# snc98_Display_15x7-Segment_LED.net
KiCad netlist of a schematic drawn in EAGLE
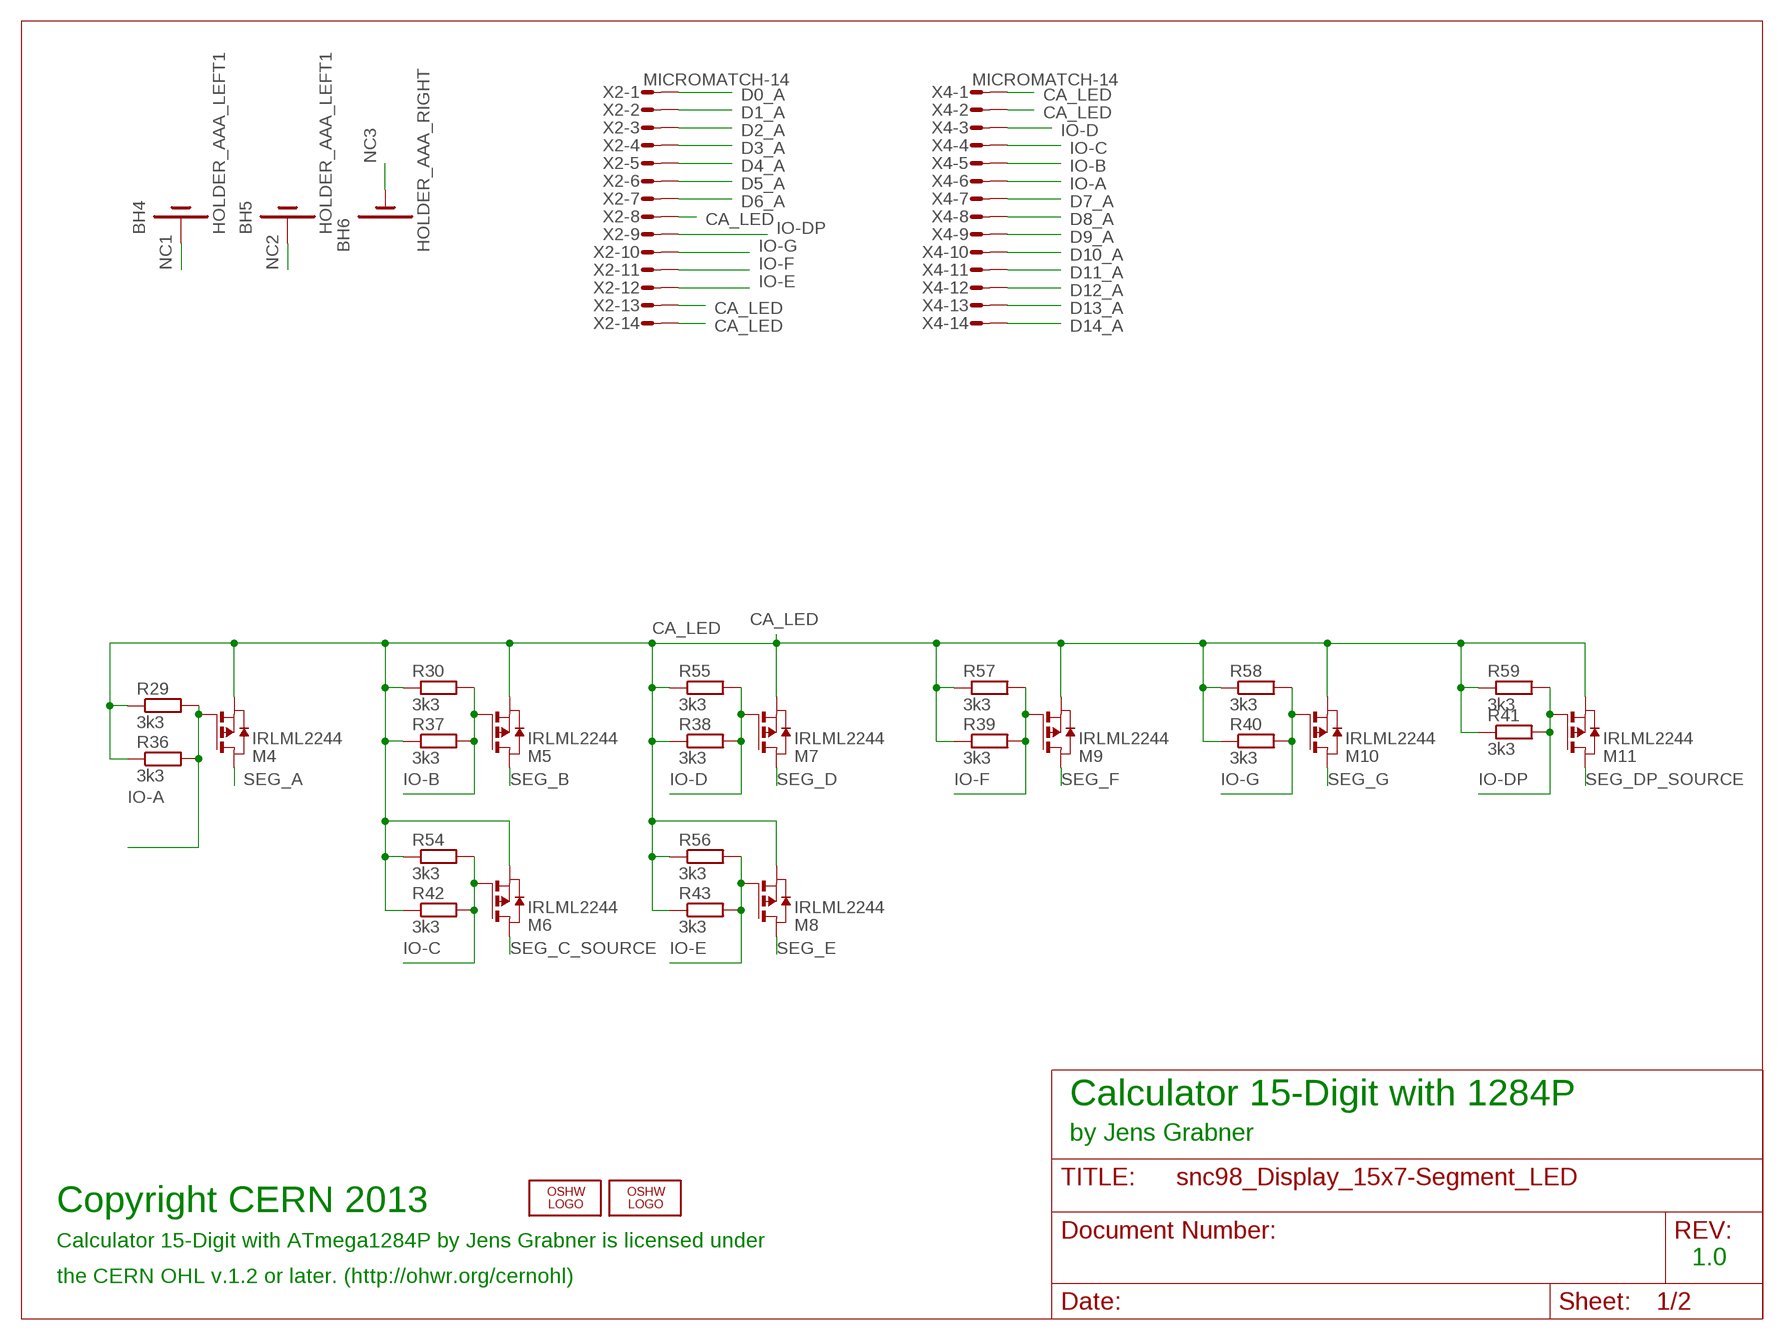
[diagram p0: schematic, sheet 1]
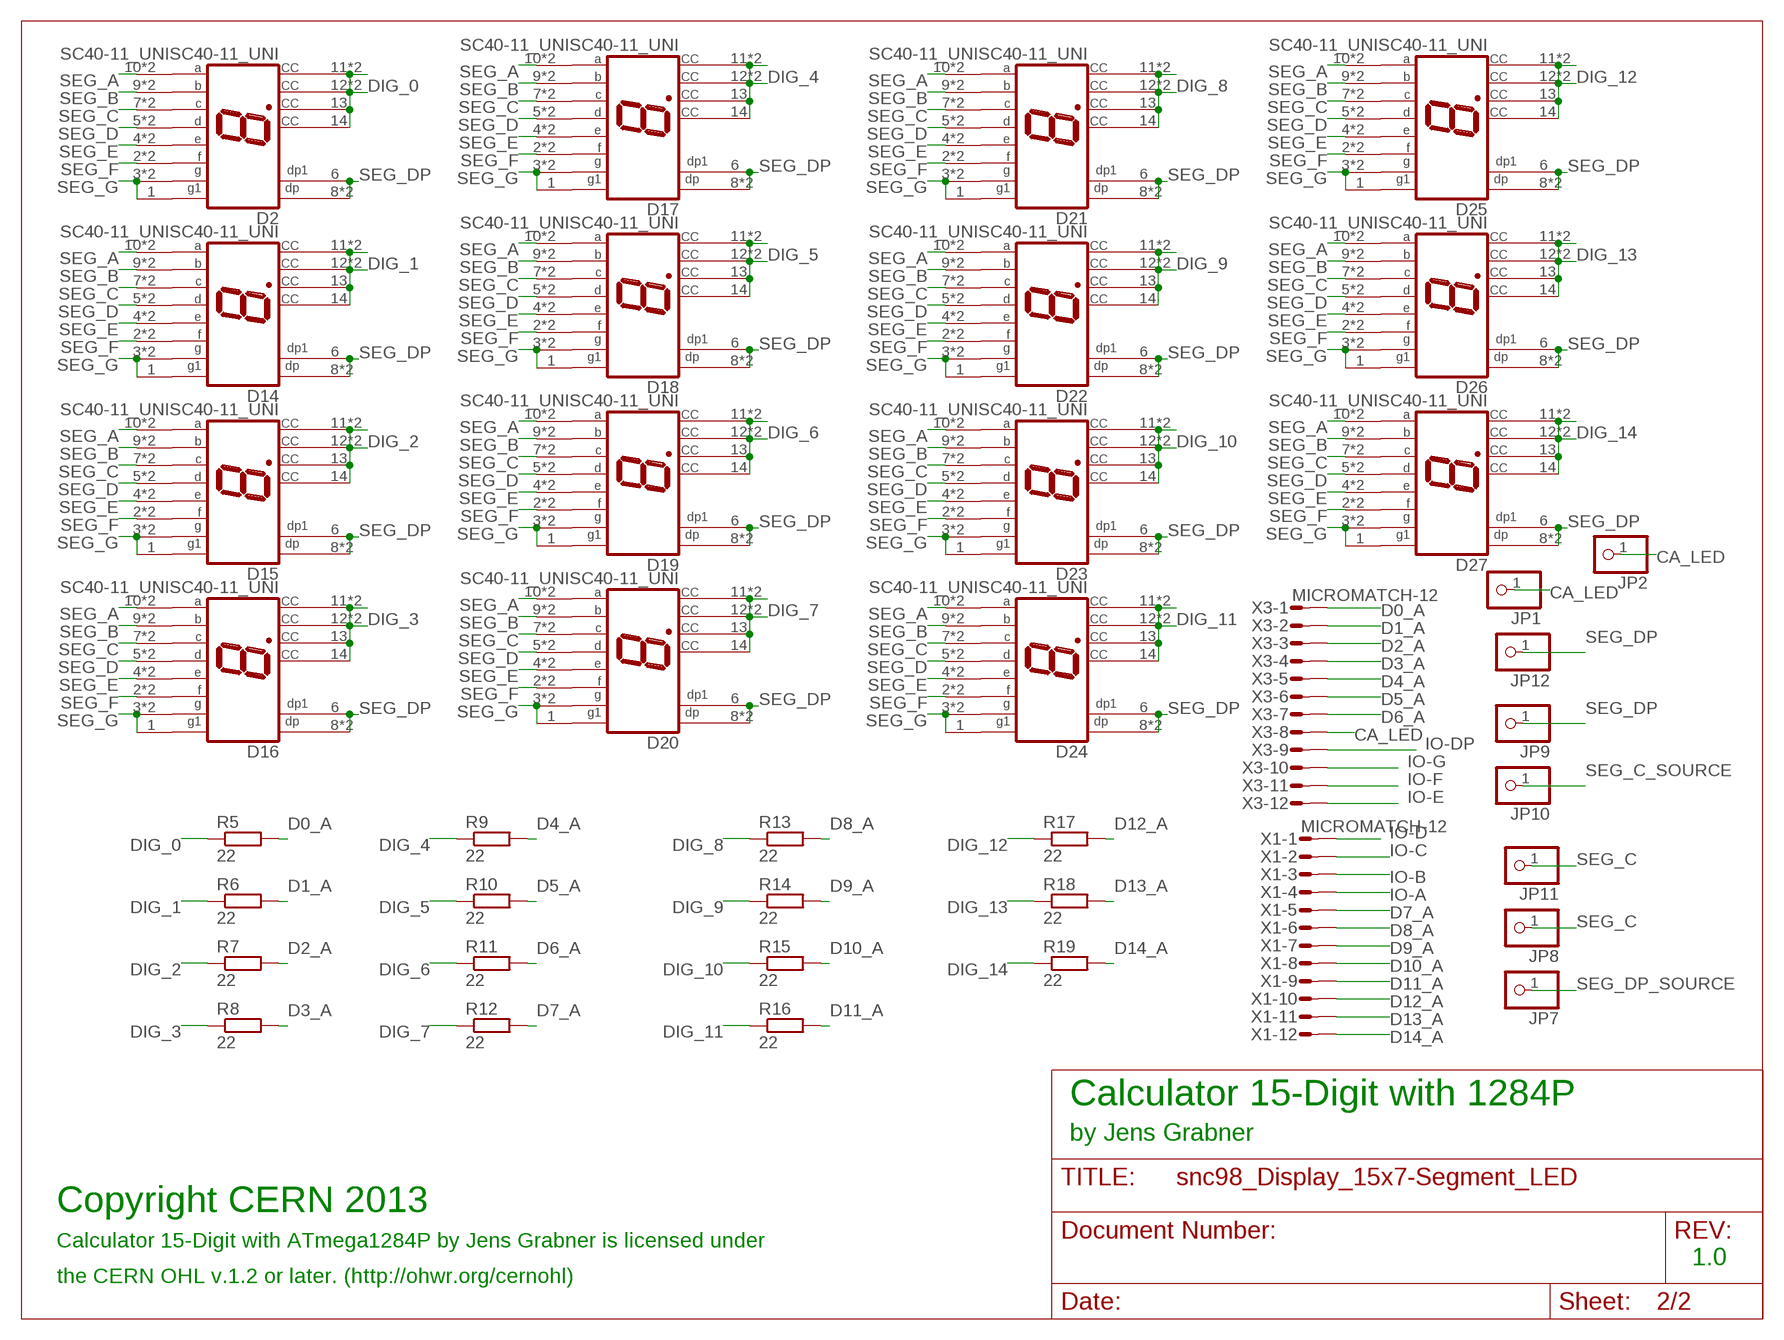
[diagram p1: schematic, sheet 2]

(export (version "E")
  (design (tool "Eeschema 10.0.6"))
  (components
    (comp (ref "BH4")
      (value "HOLDER_AAA_LEFT1")
      (footprint "eagle-import:BATTERY-AAA-LEFT")
      (libsource (lib "eagle-import") (part "HOLDER_AAA_LEFT1"))
    )
    (comp (ref "BH5")
      (value "HOLDER_AAA_LEFT1")
      (footprint "eagle-import:BATTERY-AAA-LEFT")
      (libsource (lib "eagle-import") (part "HOLDER_AAA_LEFT1"))
    )
    (comp (ref "BH6")
      (value "HOLDER_AAA_RIGHT")
      (footprint "eagle-import:BATTERY-AAA-RIGHT")
      (libsource (lib "eagle-import") (part "HOLDER_AAA_RIGHT"))
    )
    (comp (ref "LOGO1")
      (value "OSHW_LOGO_8MILX0150-NT")
      (footprint "eagle-import:OSHW_8X150_NOTEXT")
      (libsource (lib "eagle-import") (part "OSHW_LOGO_8MILX0150-NT"))
    )
    (comp (ref "LOGO3")
      (value "OSHW_LOGO_6MILX0100-NT")
      (footprint "eagle-import:OSHW_6X100_NOTEXT")
      (libsource (lib "eagle-import") (part "OSHW_LOGO_6MILX0100-NT"))
    )
    (comp (ref "M4")
      (value "IRLML2244")
      (footprint "eagle-import:SOT-23")
      (libsource (lib "eagle-import") (part "IRLML6402"))
    )
    (comp (ref "M5")
      (value "IRLML2244")
      (footprint "eagle-import:SOT-23")
      (libsource (lib "eagle-import") (part "IRLML6402"))
    )
    (comp (ref "M6")
      (value "IRLML2244")
      (footprint "eagle-import:SOT-23")
      (libsource (lib "eagle-import") (part "IRLML6402"))
    )
    (comp (ref "M7")
      (value "IRLML2244")
      (footprint "eagle-import:SOT-23")
      (libsource (lib "eagle-import") (part "IRLML6402"))
    )
    (comp (ref "M8")
      (value "IRLML2244")
      (footprint "eagle-import:SOT-23")
      (libsource (lib "eagle-import") (part "IRLML6402"))
    )
    (comp (ref "M9")
      (value "IRLML2244")
      (footprint "eagle-import:SOT-23")
      (libsource (lib "eagle-import") (part "IRLML6402"))
    )
    (comp (ref "M10")
      (value "IRLML2244")
      (footprint "eagle-import:SOT-23")
      (libsource (lib "eagle-import") (part "IRLML6402"))
    )
    (comp (ref "M11")
      (value "IRLML2244")
      (footprint "eagle-import:SOT-23")
      (libsource (lib "eagle-import") (part "IRLML6402"))
    )
    (comp (ref "R29")
      (value "3k3")
      (footprint "eagle-import:0204_5")
      (libsource (lib "eagle-import") (part "R-EU_0204/5"))
    )
    (comp (ref "R30")
      (value "3k3")
      (footprint "eagle-import:0204_5")
      (libsource (lib "eagle-import") (part "R-EU_0204/5"))
    )
    (comp (ref "R36")
      (value "3k3")
      (footprint "eagle-import:R1206")
      (libsource (lib "eagle-import") (part "R-EU_R1206"))
    )
    (comp (ref "R37")
      (value "3k3")
      (footprint "eagle-import:R1206")
      (libsource (lib "eagle-import") (part "R-EU_R1206"))
    )
    (comp (ref "R38")
      (value "3k3")
      (footprint "eagle-import:R1206")
      (libsource (lib "eagle-import") (part "R-EU_R1206"))
    )
    (comp (ref "R39")
      (value "3k3")
      (footprint "eagle-import:R1206")
      (libsource (lib "eagle-import") (part "R-EU_R1206"))
    )
    (comp (ref "R40")
      (value "3k3")
      (footprint "eagle-import:R1206")
      (libsource (lib "eagle-import") (part "R-EU_R1206"))
    )
    (comp (ref "R41")
      (value "3k3")
      (footprint "eagle-import:R1206")
      (libsource (lib "eagle-import") (part "R-EU_R1206"))
    )
    (comp (ref "R42")
      (value "3k3")
      (footprint "eagle-import:R1206")
      (libsource (lib "eagle-import") (part "R-EU_R1206"))
    )
    (comp (ref "R43")
      (value "3k3")
      (footprint "eagle-import:R1206")
      (libsource (lib "eagle-import") (part "R-EU_R1206"))
    )
    (comp (ref "R54")
      (value "3k3")
      (footprint "eagle-import:0204_5")
      (libsource (lib "eagle-import") (part "R-EU_0204/5"))
    )
    (comp (ref "R55")
      (value "3k3")
      (footprint "eagle-import:0204_5")
      (libsource (lib "eagle-import") (part "R-EU_0204/5"))
    )
    (comp (ref "R56")
      (value "3k3")
      (footprint "eagle-import:0204_5")
      (libsource (lib "eagle-import") (part "R-EU_0204/5"))
    )
    (comp (ref "R57")
      (value "3k3")
      (footprint "eagle-import:0204_5")
      (libsource (lib "eagle-import") (part "R-EU_0204/5"))
    )
    (comp (ref "R58")
      (value "3k3")
      (footprint "eagle-import:0204_5")
      (libsource (lib "eagle-import") (part "R-EU_0204/5"))
    )
    (comp (ref "R59")
      (value "3k3")
      (footprint "eagle-import:0204_5")
      (libsource (lib "eagle-import") (part "R-EU_0204/5"))
    )
    (comp (ref "X2")
      (value "MICROMATCH-14")
      (footprint "eagle-import:MICROMATCH-14")
      (fields (field (name "MF") "FARNELL") (field (name "MPN") "8-215464-4"))
      (libsource (lib "eagle-import") (part "MICROMATCH-14"))
    )
    (comp (ref "X4")
      (value "MICROMATCH-14")
      (footprint "eagle-import:MICROMATCH-14")
      (fields (field (name "MF") "FARNELL") (field (name "MPN") "8-215464-4"))
      (libsource (lib "eagle-import") (part "MICROMATCH-14"))
    )
    (comp (ref "D2")
      (value "SC40-11_UNISC40-11_UNI")
      (footprint "eagle-import:10MM_UNI")
      (libsource (lib "eagle-import") (part "SC40-11_UNISC40-11_UNI"))
    )
    (comp (ref "D14")
      (value "SC40-11_UNISC40-11_UNI")
      (footprint "eagle-import:10MM_UNI")
      (libsource (lib "eagle-import") (part "SC40-11_UNISC40-11_UNI"))
    )
    (comp (ref "D15")
      (value "SC40-11_UNISC40-11_UNI")
      (footprint "eagle-import:10MM_UNI")
      (libsource (lib "eagle-import") (part "SC40-11_UNISC40-11_UNI"))
    )
    (comp (ref "D16")
      (value "SC40-11_UNISC40-11_UNI")
      (footprint "eagle-import:10MM_UNI")
      (libsource (lib "eagle-import") (part "SC40-11_UNISC40-11_UNI"))
    )
    (comp (ref "D17")
      (value "SC40-11_UNISC40-11_UNI")
      (footprint "eagle-import:10MM_UNI")
      (libsource (lib "eagle-import") (part "SC40-11_UNISC40-11_UNI"))
    )
    (comp (ref "D18")
      (value "SC40-11_UNISC40-11_UNI")
      (footprint "eagle-import:10MM_UNI")
      (libsource (lib "eagle-import") (part "SC40-11_UNISC40-11_UNI"))
    )
    (comp (ref "D19")
      (value "SC40-11_UNISC40-11_UNI")
      (footprint "eagle-import:10MM_UNI")
      (libsource (lib "eagle-import") (part "SC40-11_UNISC40-11_UNI"))
    )
    (comp (ref "D20")
      (value "SC40-11_UNISC40-11_UNI")
      (footprint "eagle-import:10MM_UNI")
      (libsource (lib "eagle-import") (part "SC40-11_UNISC40-11_UNI"))
    )
    (comp (ref "D21")
      (value "SC40-11_UNISC40-11_UNI")
      (footprint "eagle-import:10MM_UNI")
      (libsource (lib "eagle-import") (part "SC40-11_UNISC40-11_UNI"))
    )
    (comp (ref "D22")
      (value "SC40-11_UNISC40-11_UNI")
      (footprint "eagle-import:10MM_UNI")
      (libsource (lib "eagle-import") (part "SC40-11_UNISC40-11_UNI"))
    )
    (comp (ref "D23")
      (value "SC40-11_UNISC40-11_UNI")
      (footprint "eagle-import:10MM_UNI")
      (libsource (lib "eagle-import") (part "SC40-11_UNISC40-11_UNI"))
    )
    (comp (ref "D24")
      (value "SC40-11_UNISC40-11_UNI")
      (footprint "eagle-import:10MM_UNI")
      (libsource (lib "eagle-import") (part "SC40-11_UNISC40-11_UNI"))
    )
    (comp (ref "D25")
      (value "SC40-11_UNISC40-11_UNI")
      (footprint "eagle-import:10MM_UNI")
      (libsource (lib "eagle-import") (part "SC40-11_UNISC40-11_UNI"))
    )
    (comp (ref "D26")
      (value "SC40-11_UNISC40-11_UNI")
      (footprint "eagle-import:10MM_UNI")
      (libsource (lib "eagle-import") (part "SC40-11_UNISC40-11_UNI"))
    )
    (comp (ref "D27")
      (value "SC40-11_UNISC40-11_UNI")
      (footprint "eagle-import:10MM_UNI")
      (libsource (lib "eagle-import") (part "SC40-11_UNISC40-11_UNI"))
    )
    (comp (ref "JP1")
      (value "PINHD-1X1")
      (footprint "eagle-import:1X01")
      (libsource (lib "eagle-import") (part "PINHD-1X1"))
    )
    (comp (ref "JP2")
      (value "PINHD-1X1")
      (footprint "eagle-import:1X01")
      (libsource (lib "eagle-import") (part "PINHD-1X1"))
    )
    (comp (ref "JP7")
      (value "PINHD-1X1")
      (footprint "eagle-import:1X01")
      (libsource (lib "eagle-import") (part "PINHD-1X1"))
    )
    (comp (ref "JP8")
      (value "PINHD-1X1")
      (footprint "eagle-import:1X01")
      (libsource (lib "eagle-import") (part "PINHD-1X1"))
    )
    (comp (ref "JP9")
      (value "PINHD-1X1")
      (footprint "eagle-import:1X01")
      (libsource (lib "eagle-import") (part "PINHD-1X1"))
    )
    (comp (ref "JP10")
      (value "PINHD-1X1")
      (footprint "eagle-import:1X01")
      (libsource (lib "eagle-import") (part "PINHD-1X1"))
    )
    (comp (ref "JP11")
      (value "PINHD-1X1")
      (footprint "eagle-import:1X01")
      (libsource (lib "eagle-import") (part "PINHD-1X1"))
    )
    (comp (ref "JP12")
      (value "PINHD-1X1")
      (footprint "eagle-import:1X01")
      (libsource (lib "eagle-import") (part "PINHD-1X1"))
    )
    (comp (ref "R5")
      (value "22")
      (footprint "eagle-import:R1210")
      (libsource (lib "eagle-import") (part "R-EU_R1210"))
    )
    (comp (ref "R6")
      (value "22")
      (footprint "eagle-import:R1210")
      (libsource (lib "eagle-import") (part "R-EU_R1210"))
    )
    (comp (ref "R7")
      (value "22")
      (footprint "eagle-import:R1210")
      (libsource (lib "eagle-import") (part "R-EU_R1210"))
    )
    (comp (ref "R8")
      (value "22")
      (footprint "eagle-import:R1210")
      (libsource (lib "eagle-import") (part "R-EU_R1210"))
    )
    (comp (ref "R9")
      (value "22")
      (footprint "eagle-import:R1210")
      (libsource (lib "eagle-import") (part "R-EU_R1210"))
    )
    (comp (ref "R10")
      (value "22")
      (footprint "eagle-import:R1210")
      (libsource (lib "eagle-import") (part "R-EU_R1210"))
    )
    (comp (ref "R11")
      (value "22")
      (footprint "eagle-import:R1210")
      (libsource (lib "eagle-import") (part "R-EU_R1210"))
    )
    (comp (ref "R12")
      (value "22")
      (footprint "eagle-import:R1210")
      (libsource (lib "eagle-import") (part "R-EU_R1210"))
    )
    (comp (ref "R13")
      (value "22")
      (footprint "eagle-import:R1210")
      (libsource (lib "eagle-import") (part "R-EU_R1210"))
    )
    (comp (ref "R14")
      (value "22")
      (footprint "eagle-import:R1210")
      (libsource (lib "eagle-import") (part "R-EU_R1210"))
    )
    (comp (ref "R15")
      (value "22")
      (footprint "eagle-import:R1210")
      (libsource (lib "eagle-import") (part "R-EU_R1210"))
    )
    (comp (ref "R16")
      (value "22")
      (footprint "eagle-import:R1210")
      (libsource (lib "eagle-import") (part "R-EU_R1210"))
    )
    (comp (ref "R17")
      (value "22")
      (footprint "eagle-import:R1210")
      (libsource (lib "eagle-import") (part "R-EU_R1210"))
    )
    (comp (ref "R18")
      (value "22")
      (footprint "eagle-import:R1210")
      (libsource (lib "eagle-import") (part "R-EU_R1210"))
    )
    (comp (ref "R19")
      (value "22")
      (footprint "eagle-import:R1210")
      (libsource (lib "eagle-import") (part "R-EU_R1210"))
    )
    (comp (ref "X1")
      (value "MICROMATCH-12")
      (footprint "eagle-import:MICROMATCH-12")
      (fields (field (name "MF") "FARNELL") (field (name "MPN") "8-215464-2"))
      (libsource (lib "eagle-import") (part "MICROMATCH-12"))
    )
    (comp (ref "X3")
      (value "MICROMATCH-12")
      (footprint "eagle-import:MICROMATCH-12")
      (fields (field (name "MF") "FARNELL") (field (name "MPN") "8-215464-2"))
      (libsource (lib "eagle-import") (part "MICROMATCH-12"))
    )
  )
  (nets
    (net (code "1") (name "CA_LED") (class "Default")
      (node (ref "JP1") (pin "1") (pinfunction "1_1") (pintype "passive"))
      (node (ref "JP2") (pin "1") (pinfunction "1_1") (pintype "passive"))
      (node (ref "M10") (pin "2") (pinfunction "S_2") (pintype "passive"))
      (node (ref "M11") (pin "2") (pinfunction "S_2") (pintype "passive"))
      (node (ref "M4") (pin "2") (pinfunction "S_2") (pintype "passive"))
      (node (ref "M5") (pin "2") (pinfunction "S_2") (pintype "passive"))
      (node (ref "M6") (pin "2") (pinfunction "S_2") (pintype "passive"))
      (node (ref "M7") (pin "2") (pinfunction "S_2") (pintype "passive"))
      (node (ref "M8") (pin "2") (pinfunction "S_2") (pintype "passive"))
      (node (ref "M9") (pin "2") (pinfunction "S_2") (pintype "passive"))
      (node (ref "R29") (pin "1") (pinfunction "1_1") (pintype "passive"))
      (node (ref "R30") (pin "1") (pinfunction "1_1") (pintype "passive"))
      (node (ref "R36") (pin "1") (pinfunction "1_1") (pintype "passive"))
      (node (ref "R37") (pin "1") (pinfunction "1_1") (pintype "passive"))
      (node (ref "R38") (pin "1") (pinfunction "1_1") (pintype "passive"))
      (node (ref "R39") (pin "1") (pinfunction "1_1") (pintype "passive"))
      (node (ref "R40") (pin "1") (pinfunction "1_1") (pintype "passive"))
      (node (ref "R41") (pin "1") (pinfunction "1_1") (pintype "passive"))
      (node (ref "R42") (pin "1") (pinfunction "1_1") (pintype "passive"))
      (node (ref "R43") (pin "1") (pinfunction "1_1") (pintype "passive"))
      (node (ref "R54") (pin "1") (pinfunction "1_1") (pintype "passive"))
      (node (ref "R55") (pin "1") (pinfunction "1_1") (pintype "passive"))
      (node (ref "R56") (pin "1") (pinfunction "1_1") (pintype "passive"))
      (node (ref "R57") (pin "1") (pinfunction "1_1") (pintype "passive"))
      (node (ref "R58") (pin "1") (pinfunction "1_1") (pintype "passive"))
      (node (ref "R59") (pin "1") (pinfunction "1_1") (pintype "passive"))
      (node (ref "X2") (pin "13") (pinfunction "S_13") (pintype "passive"))
      (node (ref "X2") (pin "14") (pinfunction "S_14") (pintype "passive"))
      (node (ref "X2") (pin "8") (pinfunction "S_8") (pintype "passive"))
      (node (ref "X3") (pin "8") (pinfunction "S_8") (pintype "passive"))
      (node (ref "X4") (pin "1") (pinfunction "S_1") (pintype "passive"))
      (node (ref "X4") (pin "2") (pinfunction "S_2") (pintype "passive"))
    )
    (net (code "2") (name "D0_A") (class "Default")
      (node (ref "R5") (pin "2") (pinfunction "2_2") (pintype "passive"))
      (node (ref "X2") (pin "1") (pinfunction "S_1") (pintype "passive"))
      (node (ref "X3") (pin "1") (pinfunction "S_1") (pintype "passive"))
    )
    (net (code "3") (name "D1_A") (class "Default")
      (node (ref "R6") (pin "2") (pinfunction "2_2") (pintype "passive"))
      (node (ref "X2") (pin "2") (pinfunction "S_2") (pintype "passive"))
      (node (ref "X3") (pin "2") (pinfunction "S_2") (pintype "passive"))
    )
    (net (code "4") (name "D2_A") (class "Default")
      (node (ref "R7") (pin "2") (pinfunction "2_2") (pintype "passive"))
      (node (ref "X2") (pin "3") (pinfunction "S_3") (pintype "passive"))
      (node (ref "X3") (pin "3") (pinfunction "S_3") (pintype "passive"))
    )
    (net (code "5") (name "D3_A") (class "Default")
      (node (ref "R8") (pin "2") (pinfunction "2_2") (pintype "passive"))
      (node (ref "X2") (pin "4") (pinfunction "S_4") (pintype "passive"))
      (node (ref "X3") (pin "4") (pinfunction "S_4") (pintype "passive"))
    )
    (net (code "6") (name "D4_A") (class "Default")
      (node (ref "R9") (pin "2") (pinfunction "2_2") (pintype "passive"))
      (node (ref "X2") (pin "5") (pinfunction "S_5") (pintype "passive"))
      (node (ref "X3") (pin "5") (pinfunction "S_5") (pintype "passive"))
    )
    (net (code "7") (name "D5_A") (class "Default")
      (node (ref "R10") (pin "2") (pinfunction "2_2") (pintype "passive"))
      (node (ref "X2") (pin "6") (pinfunction "S_6") (pintype "passive"))
      (node (ref "X3") (pin "6") (pinfunction "S_6") (pintype "passive"))
    )
    (net (code "8") (name "D6_A") (class "Default")
      (node (ref "R11") (pin "2") (pinfunction "2_2") (pintype "passive"))
      (node (ref "X2") (pin "7") (pinfunction "S_7") (pintype "passive"))
      (node (ref "X3") (pin "7") (pinfunction "S_7") (pintype "passive"))
    )
    (net (code "9") (name "D7_A") (class "Default")
      (node (ref "R12") (pin "2") (pinfunction "2_2") (pintype "passive"))
      (node (ref "X1") (pin "5") (pinfunction "S_5") (pintype "passive"))
      (node (ref "X4") (pin "7") (pinfunction "S_7") (pintype "passive"))
    )
    (net (code "10") (name "D8_A") (class "Default")
      (node (ref "R13") (pin "2") (pinfunction "2_2") (pintype "passive"))
      (node (ref "X1") (pin "6") (pinfunction "S_6") (pintype "passive"))
      (node (ref "X4") (pin "8") (pinfunction "S_8") (pintype "passive"))
    )
    (net (code "11") (name "D9_A") (class "Default")
      (node (ref "R14") (pin "2") (pinfunction "2_2") (pintype "passive"))
      (node (ref "X1") (pin "7") (pinfunction "S_7") (pintype "passive"))
      (node (ref "X4") (pin "9") (pinfunction "S_9") (pintype "passive"))
    )
    (net (code "12") (name "D10_A") (class "Default")
      (node (ref "R15") (pin "2") (pinfunction "2_2") (pintype "passive"))
      (node (ref "X1") (pin "8") (pinfunction "S_8") (pintype "passive"))
      (node (ref "X4") (pin "10") (pinfunction "S_10") (pintype "passive"))
    )
    (net (code "13") (name "D11_A") (class "Default")
      (node (ref "R16") (pin "2") (pinfunction "2_2") (pintype "passive"))
      (node (ref "X1") (pin "9") (pinfunction "S_9") (pintype "passive"))
      (node (ref "X4") (pin "11") (pinfunction "S_11") (pintype "passive"))
    )
    (net (code "14") (name "D12_A") (class "Default")
      (node (ref "R17") (pin "2") (pinfunction "2_2") (pintype "passive"))
      (node (ref "X1") (pin "10") (pinfunction "S_10") (pintype "passive"))
      (node (ref "X4") (pin "12") (pinfunction "S_12") (pintype "passive"))
    )
    (net (code "15") (name "D13_A") (class "Default")
      (node (ref "R18") (pin "2") (pinfunction "2_2") (pintype "passive"))
      (node (ref "X1") (pin "11") (pinfunction "S_11") (pintype "passive"))
      (node (ref "X4") (pin "13") (pinfunction "S_13") (pintype "passive"))
    )
    (net (code "16") (name "D14_A") (class "Default")
      (node (ref "R19") (pin "2") (pinfunction "2_2") (pintype "passive"))
      (node (ref "X1") (pin "12") (pinfunction "S_12") (pintype "passive"))
      (node (ref "X4") (pin "14") (pinfunction "S_14") (pintype "passive"))
    )
    (net (code "17") (name "DIG_0") (class "Default")
      (node (ref "D2") (pin "11") (pinfunction "CC1_11") (pintype "passive"))
      (node (ref "D2") (pin "12") (pinfunction "CC2_12") (pintype "passive"))
      (node (ref "D2") (pin "13") (pinfunction "CC3_13") (pintype "passive"))
      (node (ref "D2") (pin "14") (pinfunction "CC4_14") (pintype "passive"))
      (node (ref "D2") (pin "23") (pinfunction "CC1_23") (pintype "passive"))
      (node (ref "D2") (pin "28") (pinfunction "CC2_28") (pintype "passive"))
      (node (ref "R5") (pin "1") (pinfunction "1_1") (pintype "passive"))
    )
    (net (code "18") (name "DIG_1") (class "Default")
      (node (ref "D14") (pin "11") (pinfunction "CC1_11") (pintype "passive"))
      (node (ref "D14") (pin "12") (pinfunction "CC2_12") (pintype "passive"))
      (node (ref "D14") (pin "13") (pinfunction "CC3_13") (pintype "passive"))
      (node (ref "D14") (pin "14") (pinfunction "CC4_14") (pintype "passive"))
      (node (ref "D14") (pin "23") (pinfunction "CC1_23") (pintype "passive"))
      (node (ref "D14") (pin "28") (pinfunction "CC2_28") (pintype "passive"))
      (node (ref "R6") (pin "1") (pinfunction "1_1") (pintype "passive"))
    )
    (net (code "19") (name "DIG_2") (class "Default")
      (node (ref "D15") (pin "11") (pinfunction "CC1_11") (pintype "passive"))
      (node (ref "D15") (pin "12") (pinfunction "CC2_12") (pintype "passive"))
      (node (ref "D15") (pin "13") (pinfunction "CC3_13") (pintype "passive"))
      (node (ref "D15") (pin "14") (pinfunction "CC4_14") (pintype "passive"))
      (node (ref "D15") (pin "23") (pinfunction "CC1_23") (pintype "passive"))
      (node (ref "D15") (pin "28") (pinfunction "CC2_28") (pintype "passive"))
      (node (ref "R7") (pin "1") (pinfunction "1_1") (pintype "passive"))
    )
    (net (code "20") (name "DIG_3") (class "Default")
      (node (ref "D16") (pin "11") (pinfunction "CC1_11") (pintype "passive"))
      (node (ref "D16") (pin "12") (pinfunction "CC2_12") (pintype "passive"))
      (node (ref "D16") (pin "13") (pinfunction "CC3_13") (pintype "passive"))
      (node (ref "D16") (pin "14") (pinfunction "CC4_14") (pintype "passive"))
      (node (ref "D16") (pin "23") (pinfunction "CC1_23") (pintype "passive"))
      (node (ref "D16") (pin "28") (pinfunction "CC2_28") (pintype "passive"))
      (node (ref "R8") (pin "1") (pinfunction "1_1") (pintype "passive"))
    )
    (net (code "21") (name "DIG_4") (class "Default")
      (node (ref "D17") (pin "11") (pinfunction "CC1_11") (pintype "passive"))
      (node (ref "D17") (pin "12") (pinfunction "CC2_12") (pintype "passive"))
      (node (ref "D17") (pin "13") (pinfunction "CC3_13") (pintype "passive"))
      (node (ref "D17") (pin "14") (pinfunction "CC4_14") (pintype "passive"))
      (node (ref "D17") (pin "23") (pinfunction "CC1_23") (pintype "passive"))
      (node (ref "D17") (pin "28") (pinfunction "CC2_28") (pintype "passive"))
      (node (ref "R9") (pin "1") (pinfunction "1_1") (pintype "passive"))
    )
    (net (code "22") (name "DIG_5") (class "Default")
      (node (ref "D18") (pin "11") (pinfunction "CC1_11") (pintype "passive"))
      (node (ref "D18") (pin "12") (pinfunction "CC2_12") (pintype "passive"))
      (node (ref "D18") (pin "13") (pinfunction "CC3_13") (pintype "passive"))
      (node (ref "D18") (pin "14") (pinfunction "CC4_14") (pintype "passive"))
      (node (ref "D18") (pin "23") (pinfunction "CC1_23") (pintype "passive"))
      (node (ref "D18") (pin "28") (pinfunction "CC2_28") (pintype "passive"))
      (node (ref "R10") (pin "1") (pinfunction "1_1") (pintype "passive"))
    )
    (net (code "23") (name "DIG_6") (class "Default")
      (node (ref "D19") (pin "11") (pinfunction "CC1_11") (pintype "passive"))
      (node (ref "D19") (pin "12") (pinfunction "CC2_12") (pintype "passive"))
      (node (ref "D19") (pin "13") (pinfunction "CC3_13") (pintype "passive"))
      (node (ref "D19") (pin "14") (pinfunction "CC4_14") (pintype "passive"))
      (node (ref "D19") (pin "23") (pinfunction "CC1_23") (pintype "passive"))
      (node (ref "D19") (pin "28") (pinfunction "CC2_28") (pintype "passive"))
      (node (ref "R11") (pin "1") (pinfunction "1_1") (pintype "passive"))
    )
    (net (code "24") (name "DIG_7") (class "Default")
      (node (ref "D20") (pin "11") (pinfunction "CC1_11") (pintype "passive"))
      (node (ref "D20") (pin "12") (pinfunction "CC2_12") (pintype "passive"))
      (node (ref "D20") (pin "13") (pinfunction "CC3_13") (pintype "passive"))
      (node (ref "D20") (pin "14") (pinfunction "CC4_14") (pintype "passive"))
      (node (ref "D20") (pin "23") (pinfunction "CC1_23") (pintype "passive"))
      (node (ref "D20") (pin "28") (pinfunction "CC2_28") (pintype "passive"))
      (node (ref "R12") (pin "1") (pinfunction "1_1") (pintype "passive"))
    )
    (net (code "25") (name "DIG_8") (class "Default")
      (node (ref "D21") (pin "11") (pinfunction "CC1_11") (pintype "passive"))
      (node (ref "D21") (pin "12") (pinfunction "CC2_12") (pintype "passive"))
      (node (ref "D21") (pin "13") (pinfunction "CC3_13") (pintype "passive"))
      (node (ref "D21") (pin "14") (pinfunction "CC4_14") (pintype "passive"))
      (node (ref "D21") (pin "23") (pinfunction "CC1_23") (pintype "passive"))
      (node (ref "D21") (pin "28") (pinfunction "CC2_28") (pintype "passive"))
      (node (ref "R13") (pin "1") (pinfunction "1_1") (pintype "passive"))
    )
    (net (code "26") (name "DIG_9") (class "Default")
      (node (ref "D22") (pin "11") (pinfunction "CC1_11") (pintype "passive"))
      (node (ref "D22") (pin "12") (pinfunction "CC2_12") (pintype "passive"))
      (node (ref "D22") (pin "13") (pinfunction "CC3_13") (pintype "passive"))
      (node (ref "D22") (pin "14") (pinfunction "CC4_14") (pintype "passive"))
      (node (ref "D22") (pin "23") (pinfunction "CC1_23") (pintype "passive"))
      (node (ref "D22") (pin "28") (pinfunction "CC2_28") (pintype "passive"))
      (node (ref "R14") (pin "1") (pinfunction "1_1") (pintype "passive"))
    )
    (net (code "27") (name "DIG_10") (class "Default")
      (node (ref "D23") (pin "11") (pinfunction "CC1_11") (pintype "passive"))
      (node (ref "D23") (pin "12") (pinfunction "CC2_12") (pintype "passive"))
      (node (ref "D23") (pin "13") (pinfunction "CC3_13") (pintype "passive"))
      (node (ref "D23") (pin "14") (pinfunction "CC4_14") (pintype "passive"))
      (node (ref "D23") (pin "23") (pinfunction "CC1_23") (pintype "passive"))
      (node (ref "D23") (pin "28") (pinfunction "CC2_28") (pintype "passive"))
      (node (ref "R15") (pin "1") (pinfunction "1_1") (pintype "passive"))
    )
    (net (code "28") (name "DIG_11") (class "Default")
      (node (ref "D24") (pin "11") (pinfunction "CC1_11") (pintype "passive"))
      (node (ref "D24") (pin "12") (pinfunction "CC2_12") (pintype "passive"))
      (node (ref "D24") (pin "13") (pinfunction "CC3_13") (pintype "passive"))
      (node (ref "D24") (pin "14") (pinfunction "CC4_14") (pintype "passive"))
      (node (ref "D24") (pin "23") (pinfunction "CC1_23") (pintype "passive"))
      (node (ref "D24") (pin "28") (pinfunction "CC2_28") (pintype "passive"))
      (node (ref "R16") (pin "1") (pinfunction "1_1") (pintype "passive"))
    )
    (net (code "29") (name "DIG_12") (class "Default")
      (node (ref "D25") (pin "11") (pinfunction "CC1_11") (pintype "passive"))
      (node (ref "D25") (pin "12") (pinfunction "CC2_12") (pintype "passive"))
      (node (ref "D25") (pin "13") (pinfunction "CC3_13") (pintype "passive"))
      (node (ref "D25") (pin "14") (pinfunction "CC4_14") (pintype "passive"))
      (node (ref "D25") (pin "23") (pinfunction "CC1_23") (pintype "passive"))
      (node (ref "D25") (pin "28") (pinfunction "CC2_28") (pintype "passive"))
      (node (ref "R17") (pin "1") (pinfunction "1_1") (pintype "passive"))
    )
    (net (code "30") (name "DIG_13") (class "Default")
      (node (ref "D26") (pin "11") (pinfunction "CC1_11") (pintype "passive"))
      (node (ref "D26") (pin "12") (pinfunction "CC2_12") (pintype "passive"))
      (node (ref "D26") (pin "13") (pinfunction "CC3_13") (pintype "passive"))
      (node (ref "D26") (pin "14") (pinfunction "CC4_14") (pintype "passive"))
      (node (ref "D26") (pin "23") (pinfunction "CC1_23") (pintype "passive"))
      (node (ref "D26") (pin "28") (pinfunction "CC2_28") (pintype "passive"))
      (node (ref "R18") (pin "1") (pinfunction "1_1") (pintype "passive"))
    )
    (net (code "31") (name "DIG_14") (class "Default")
      (node (ref "D27") (pin "11") (pinfunction "CC1_11") (pintype "passive"))
      (node (ref "D27") (pin "12") (pinfunction "CC2_12") (pintype "passive"))
      (node (ref "D27") (pin "13") (pinfunction "CC3_13") (pintype "passive"))
      (node (ref "D27") (pin "14") (pinfunction "CC4_14") (pintype "passive"))
      (node (ref "D27") (pin "23") (pinfunction "CC1_23") (pintype "passive"))
      (node (ref "D27") (pin "28") (pinfunction "CC2_28") (pintype "passive"))
      (node (ref "R19") (pin "1") (pinfunction "1_1") (pintype "passive"))
    )
    (net (code "32") (name "IO-A") (class "Default")
      (node (ref "M4") (pin "1") (pinfunction "G_1") (pintype "passive"))
      (node (ref "R29") (pin "2") (pinfunction "2_2") (pintype "passive"))
      (node (ref "R36") (pin "2") (pinfunction "2_2") (pintype "passive"))
      (node (ref "X1") (pin "4") (pinfunction "S_4") (pintype "passive"))
      (node (ref "X4") (pin "6") (pinfunction "S_6") (pintype "passive"))
    )
    (net (code "33") (name "IO-B") (class "Default")
      (node (ref "M5") (pin "1") (pinfunction "G_1") (pintype "passive"))
      (node (ref "R30") (pin "2") (pinfunction "2_2") (pintype "passive"))
      (node (ref "R37") (pin "2") (pinfunction "2_2") (pintype "passive"))
      (node (ref "X1") (pin "3") (pinfunction "S_3") (pintype "passive"))
      (node (ref "X4") (pin "5") (pinfunction "S_5") (pintype "passive"))
    )
    (net (code "34") (name "IO-C") (class "Default")
      (node (ref "M6") (pin "1") (pinfunction "G_1") (pintype "passive"))
      (node (ref "R42") (pin "2") (pinfunction "2_2") (pintype "passive"))
      (node (ref "R54") (pin "2") (pinfunction "2_2") (pintype "passive"))
      (node (ref "X1") (pin "2") (pinfunction "S_2") (pintype "passive"))
      (node (ref "X4") (pin "4") (pinfunction "S_4") (pintype "passive"))
    )
    (net (code "35") (name "IO-D") (class "Default")
      (node (ref "M7") (pin "1") (pinfunction "G_1") (pintype "passive"))
      (node (ref "R38") (pin "2") (pinfunction "2_2") (pintype "passive"))
      (node (ref "R55") (pin "2") (pinfunction "2_2") (pintype "passive"))
      (node (ref "X1") (pin "1") (pinfunction "S_1") (pintype "passive"))
      (node (ref "X4") (pin "3") (pinfunction "S_3") (pintype "passive"))
    )
    (net (code "36") (name "IO-DP") (class "Default")
      (node (ref "M11") (pin "1") (pinfunction "G_1") (pintype "passive"))
      (node (ref "R41") (pin "2") (pinfunction "2_2") (pintype "passive"))
      (node (ref "R59") (pin "2") (pinfunction "2_2") (pintype "passive"))
      (node (ref "X2") (pin "9") (pinfunction "S_9") (pintype "passive"))
      (node (ref "X3") (pin "9") (pinfunction "S_9") (pintype "passive"))
    )
    (net (code "37") (name "IO-E") (class "Default")
      (node (ref "M8") (pin "1") (pinfunction "G_1") (pintype "passive"))
      (node (ref "R43") (pin "2") (pinfunction "2_2") (pintype "passive"))
      (node (ref "R56") (pin "2") (pinfunction "2_2") (pintype "passive"))
      (node (ref "X2") (pin "12") (pinfunction "S_12") (pintype "passive"))
      (node (ref "X3") (pin "12") (pinfunction "S_12") (pintype "passive"))
    )
    (net (code "38") (name "IO-F") (class "Default")
      (node (ref "M9") (pin "1") (pinfunction "G_1") (pintype "passive"))
      (node (ref "R39") (pin "2") (pinfunction "2_2") (pintype "passive"))
      (node (ref "R57") (pin "2") (pinfunction "2_2") (pintype "passive"))
      (node (ref "X2") (pin "11") (pinfunction "S_11") (pintype "passive"))
      (node (ref "X3") (pin "11") (pinfunction "S_11") (pintype "passive"))
    )
    (net (code "39") (name "IO-G") (class "Default")
      (node (ref "M10") (pin "1") (pinfunction "G_1") (pintype "passive"))
      (node (ref "R40") (pin "2") (pinfunction "2_2") (pintype "passive"))
      (node (ref "R58") (pin "2") (pinfunction "2_2") (pintype "passive"))
      (node (ref "X2") (pin "10") (pinfunction "S_10") (pintype "passive"))
      (node (ref "X3") (pin "10") (pinfunction "S_10") (pintype "passive"))
    )
    (net (code "40") (name "NC1") (class "Default")
      (node (ref "BH4") (pin "P1") (pinfunction "+_P1") (pintype "power_in"))
      (node (ref "BH4") (pin "P2") (pinfunction "+_P2") (pintype "power_in"))
      (node (ref "BH4") (pin "P3") (pinfunction "+_P3") (pintype "power_in"))
      (node (ref "BH4") (pin "P4") (pinfunction "+_P4") (pintype "power_in"))
    )
    (net (code "41") (name "NC2") (class "Default")
      (node (ref "BH5") (pin "P1") (pinfunction "+_P1") (pintype "power_in"))
      (node (ref "BH5") (pin "P2") (pinfunction "+_P2") (pintype "power_in"))
      (node (ref "BH5") (pin "P3") (pinfunction "+_P3") (pintype "power_in"))
      (node (ref "BH5") (pin "P4") (pinfunction "+_P4") (pintype "power_in"))
    )
    (net (code "42") (name "NC3") (class "Default")
      (node (ref "BH6") (pin "M1") (pinfunction "-_M1") (pintype "power_in"))
      (node (ref "BH6") (pin "M2") (pinfunction "-_M2") (pintype "power_in"))
      (node (ref "BH6") (pin "M3") (pinfunction "-_M3") (pintype "power_in"))
      (node (ref "BH6") (pin "M4") (pinfunction "-_M4") (pintype "power_in"))
    )
    (net (code "43") (name "SEG_A") (class "Default")
      (node (ref "D14") (pin "10") (pinfunction "A_10") (pintype "passive"))
      (node (ref "D14") (pin "27") (pinfunction "A_27") (pintype "passive"))
      (node (ref "D15") (pin "10") (pinfunction "A_10") (pintype "passive"))
      (node (ref "D15") (pin "27") (pinfunction "A_27") (pintype "passive"))
      (node (ref "D16") (pin "10") (pinfunction "A_10") (pintype "passive"))
      (node (ref "D16") (pin "27") (pinfunction "A_27") (pintype "passive"))
      (node (ref "D17") (pin "10") (pinfunction "A_10") (pintype "passive"))
      (node (ref "D17") (pin "27") (pinfunction "A_27") (pintype "passive"))
      (node (ref "D18") (pin "10") (pinfunction "A_10") (pintype "passive"))
      (node (ref "D18") (pin "27") (pinfunction "A_27") (pintype "passive"))
      (node (ref "D19") (pin "10") (pinfunction "A_10") (pintype "passive"))
      (node (ref "D19") (pin "27") (pinfunction "A_27") (pintype "passive"))
      (node (ref "D2") (pin "10") (pinfunction "A_10") (pintype "passive"))
      (node (ref "D2") (pin "27") (pinfunction "A_27") (pintype "passive"))
      (node (ref "D20") (pin "10") (pinfunction "A_10") (pintype "passive"))
      (node (ref "D20") (pin "27") (pinfunction "A_27") (pintype "passive"))
      (node (ref "D21") (pin "10") (pinfunction "A_10") (pintype "passive"))
      (node (ref "D21") (pin "27") (pinfunction "A_27") (pintype "passive"))
      (node (ref "D22") (pin "10") (pinfunction "A_10") (pintype "passive"))
      (node (ref "D22") (pin "27") (pinfunction "A_27") (pintype "passive"))
      (node (ref "D23") (pin "10") (pinfunction "A_10") (pintype "passive"))
      (node (ref "D23") (pin "27") (pinfunction "A_27") (pintype "passive"))
      (node (ref "D24") (pin "10") (pinfunction "A_10") (pintype "passive"))
      (node (ref "D24") (pin "27") (pinfunction "A_27") (pintype "passive"))
      (node (ref "D25") (pin "10") (pinfunction "A_10") (pintype "passive"))
      (node (ref "D25") (pin "27") (pinfunction "A_27") (pintype "passive"))
      (node (ref "D26") (pin "10") (pinfunction "A_10") (pintype "passive"))
      (node (ref "D26") (pin "27") (pinfunction "A_27") (pintype "passive"))
      (node (ref "D27") (pin "10") (pinfunction "A_10") (pintype "passive"))
      (node (ref "D27") (pin "27") (pinfunction "A_27") (pintype "passive"))
      (node (ref "M4") (pin "3") (pinfunction "D_3") (pintype "passive"))
    )
    (net (code "44") (name "SEG_B") (class "Default")
      (node (ref "D14") (pin "26") (pinfunction "B_26") (pintype "passive"))
      (node (ref "D14") (pin "9") (pinfunction "B_9") (pintype "passive"))
      (node (ref "D15") (pin "26") (pinfunction "B_26") (pintype "passive"))
      (node (ref "D15") (pin "9") (pinfunction "B_9") (pintype "passive"))
      (node (ref "D16") (pin "26") (pinfunction "B_26") (pintype "passive"))
      (node (ref "D16") (pin "9") (pinfunction "B_9") (pintype "passive"))
      (node (ref "D17") (pin "26") (pinfunction "B_26") (pintype "passive"))
      (node (ref "D17") (pin "9") (pinfunction "B_9") (pintype "passive"))
      (node (ref "D18") (pin "26") (pinfunction "B_26") (pintype "passive"))
      (node (ref "D18") (pin "9") (pinfunction "B_9") (pintype "passive"))
      (node (ref "D19") (pin "26") (pinfunction "B_26") (pintype "passive"))
      (node (ref "D19") (pin "9") (pinfunction "B_9") (pintype "passive"))
      (node (ref "D2") (pin "26") (pinfunction "B_26") (pintype "passive"))
      (node (ref "D2") (pin "9") (pinfunction "B_9") (pintype "passive"))
      (node (ref "D20") (pin "26") (pinfunction "B_26") (pintype "passive"))
      (node (ref "D20") (pin "9") (pinfunction "B_9") (pintype "passive"))
      (node (ref "D21") (pin "26") (pinfunction "B_26") (pintype "passive"))
      (node (ref "D21") (pin "9") (pinfunction "B_9") (pintype "passive"))
      (node (ref "D22") (pin "26") (pinfunction "B_26") (pintype "passive"))
      (node (ref "D22") (pin "9") (pinfunction "B_9") (pintype "passive"))
      (node (ref "D23") (pin "26") (pinfunction "B_26") (pintype "passive"))
      (node (ref "D23") (pin "9") (pinfunction "B_9") (pintype "passive"))
      (node (ref "D24") (pin "26") (pinfunction "B_26") (pintype "passive"))
      (node (ref "D24") (pin "9") (pinfunction "B_9") (pintype "passive"))
      (node (ref "D25") (pin "26") (pinfunction "B_26") (pintype "passive"))
      (node (ref "D25") (pin "9") (pinfunction "B_9") (pintype "passive"))
      (node (ref "D26") (pin "26") (pinfunction "B_26") (pintype "passive"))
      (node (ref "D26") (pin "9") (pinfunction "B_9") (pintype "passive"))
      (node (ref "D27") (pin "26") (pinfunction "B_26") (pintype "passive"))
      (node (ref "D27") (pin "9") (pinfunction "B_9") (pintype "passive"))
      (node (ref "M5") (pin "3") (pinfunction "D_3") (pintype "passive"))
    )
    (net (code "45") (name "SEG_C") (class "Default")
      (node (ref "D14") (pin "24") (pinfunction "C_24") (pintype "passive"))
      (node (ref "D14") (pin "7") (pinfunction "C_7") (pintype "passive"))
      (node (ref "D15") (pin "24") (pinfunction "C_24") (pintype "passive"))
      (node (ref "D15") (pin "7") (pinfunction "C_7") (pintype "passive"))
      (node (ref "D16") (pin "24") (pinfunction "C_24") (pintype "passive"))
      (node (ref "D16") (pin "7") (pinfunction "C_7") (pintype "passive"))
      (node (ref "D17") (pin "24") (pinfunction "C_24") (pintype "passive"))
      (node (ref "D17") (pin "7") (pinfunction "C_7") (pintype "passive"))
      (node (ref "D18") (pin "24") (pinfunction "C_24") (pintype "passive"))
      (node (ref "D18") (pin "7") (pinfunction "C_7") (pintype "passive"))
      (node (ref "D19") (pin "24") (pinfunction "C_24") (pintype "passive"))
      (node (ref "D19") (pin "7") (pinfunction "C_7") (pintype "passive"))
      (node (ref "D2") (pin "24") (pinfunction "C_24") (pintype "passive"))
      (node (ref "D2") (pin "7") (pinfunction "C_7") (pintype "passive"))
      (node (ref "D20") (pin "24") (pinfunction "C_24") (pintype "passive"))
      (node (ref "D20") (pin "7") (pinfunction "C_7") (pintype "passive"))
      (node (ref "D21") (pin "24") (pinfunction "C_24") (pintype "passive"))
      (node (ref "D21") (pin "7") (pinfunction "C_7") (pintype "passive"))
      (node (ref "D22") (pin "24") (pinfunction "C_24") (pintype "passive"))
      (node (ref "D22") (pin "7") (pinfunction "C_7") (pintype "passive"))
      (node (ref "D23") (pin "24") (pinfunction "C_24") (pintype "passive"))
      (node (ref "D23") (pin "7") (pinfunction "C_7") (pintype "passive"))
      (node (ref "D24") (pin "24") (pinfunction "C_24") (pintype "passive"))
      (node (ref "D24") (pin "7") (pinfunction "C_7") (pintype "passive"))
      (node (ref "D25") (pin "24") (pinfunction "C_24") (pintype "passive"))
      (node (ref "D25") (pin "7") (pinfunction "C_7") (pintype "passive"))
      (node (ref "D26") (pin "24") (pinfunction "C_24") (pintype "passive"))
      (node (ref "D26") (pin "7") (pinfunction "C_7") (pintype "passive"))
      (node (ref "D27") (pin "24") (pinfunction "C_24") (pintype "passive"))
      (node (ref "D27") (pin "7") (pinfunction "C_7") (pintype "passive"))
      (node (ref "JP11") (pin "1") (pinfunction "1_1") (pintype "passive"))
      (node (ref "JP8") (pin "1") (pinfunction "1_1") (pintype "passive"))
    )
    (net (code "46") (name "SEG_C_SOURCE") (class "Default")
      (node (ref "JP10") (pin "1") (pinfunction "1_1") (pintype "passive"))
      (node (ref "M6") (pin "3") (pinfunction "D_3") (pintype "passive"))
    )
    (net (code "47") (name "SEG_D") (class "Default")
      (node (ref "D14") (pin "22") (pinfunction "D_22") (pintype "passive"))
      (node (ref "D14") (pin "5") (pinfunction "D_5") (pintype "passive"))
      (node (ref "D15") (pin "22") (pinfunction "D_22") (pintype "passive"))
      (node (ref "D15") (pin "5") (pinfunction "D_5") (pintype "passive"))
      (node (ref "D16") (pin "22") (pinfunction "D_22") (pintype "passive"))
      (node (ref "D16") (pin "5") (pinfunction "D_5") (pintype "passive"))
      (node (ref "D17") (pin "22") (pinfunction "D_22") (pintype "passive"))
      (node (ref "D17") (pin "5") (pinfunction "D_5") (pintype "passive"))
      (node (ref "D18") (pin "22") (pinfunction "D_22") (pintype "passive"))
      (node (ref "D18") (pin "5") (pinfunction "D_5") (pintype "passive"))
      (node (ref "D19") (pin "22") (pinfunction "D_22") (pintype "passive"))
      (node (ref "D19") (pin "5") (pinfunction "D_5") (pintype "passive"))
      (node (ref "D2") (pin "22") (pinfunction "D_22") (pintype "passive"))
      (node (ref "D2") (pin "5") (pinfunction "D_5") (pintype "passive"))
      (node (ref "D20") (pin "22") (pinfunction "D_22") (pintype "passive"))
      (node (ref "D20") (pin "5") (pinfunction "D_5") (pintype "passive"))
      (node (ref "D21") (pin "22") (pinfunction "D_22") (pintype "passive"))
      (node (ref "D21") (pin "5") (pinfunction "D_5") (pintype "passive"))
      (node (ref "D22") (pin "22") (pinfunction "D_22") (pintype "passive"))
      (node (ref "D22") (pin "5") (pinfunction "D_5") (pintype "passive"))
      (node (ref "D23") (pin "22") (pinfunction "D_22") (pintype "passive"))
      (node (ref "D23") (pin "5") (pinfunction "D_5") (pintype "passive"))
      (node (ref "D24") (pin "22") (pinfunction "D_22") (pintype "passive"))
      (node (ref "D24") (pin "5") (pinfunction "D_5") (pintype "passive"))
      (node (ref "D25") (pin "22") (pinfunction "D_22") (pintype "passive"))
      (node (ref "D25") (pin "5") (pinfunction "D_5") (pintype "passive"))
      (node (ref "D26") (pin "22") (pinfunction "D_22") (pintype "passive"))
      (node (ref "D26") (pin "5") (pinfunction "D_5") (pintype "passive"))
      (node (ref "D27") (pin "22") (pinfunction "D_22") (pintype "passive"))
      (node (ref "D27") (pin "5") (pinfunction "D_5") (pintype "passive"))
      (node (ref "M7") (pin "3") (pinfunction "D_3") (pintype "passive"))
    )
    (net (code "48") (name "SEG_DP") (class "Default")
      (node (ref "D14") (pin "25") (pinfunction "DP_25") (pintype "passive"))
      (node (ref "D14") (pin "6") (pinfunction "DP1_6") (pintype "passive"))
      (node (ref "D14") (pin "8") (pinfunction "DP_8") (pintype "passive"))
      (node (ref "D15") (pin "25") (pinfunction "DP_25") (pintype "passive"))
      (node (ref "D15") (pin "6") (pinfunction "DP1_6") (pintype "passive"))
      (node (ref "D15") (pin "8") (pinfunction "DP_8") (pintype "passive"))
      (node (ref "D16") (pin "25") (pinfunction "DP_25") (pintype "passive"))
      (node (ref "D16") (pin "6") (pinfunction "DP1_6") (pintype "passive"))
      (node (ref "D16") (pin "8") (pinfunction "DP_8") (pintype "passive"))
      (node (ref "D17") (pin "25") (pinfunction "DP_25") (pintype "passive"))
      (node (ref "D17") (pin "6") (pinfunction "DP1_6") (pintype "passive"))
      (node (ref "D17") (pin "8") (pinfunction "DP_8") (pintype "passive"))
      (node (ref "D18") (pin "25") (pinfunction "DP_25") (pintype "passive"))
      (node (ref "D18") (pin "6") (pinfunction "DP1_6") (pintype "passive"))
      (node (ref "D18") (pin "8") (pinfunction "DP_8") (pintype "passive"))
      (node (ref "D19") (pin "25") (pinfunction "DP_25") (pintype "passive"))
      (node (ref "D19") (pin "6") (pinfunction "DP1_6") (pintype "passive"))
      (node (ref "D19") (pin "8") (pinfunction "DP_8") (pintype "passive"))
      (node (ref "D2") (pin "25") (pinfunction "DP_25") (pintype "passive"))
      (node (ref "D2") (pin "6") (pinfunction "DP1_6") (pintype "passive"))
      (node (ref "D2") (pin "8") (pinfunction "DP_8") (pintype "passive"))
      (node (ref "D20") (pin "25") (pinfunction "DP_25") (pintype "passive"))
      (node (ref "D20") (pin "6") (pinfunction "DP1_6") (pintype "passive"))
      (node (ref "D20") (pin "8") (pinfunction "DP_8") (pintype "passive"))
      (node (ref "D21") (pin "25") (pinfunction "DP_25") (pintype "passive"))
      (node (ref "D21") (pin "6") (pinfunction "DP1_6") (pintype "passive"))
      (node (ref "D21") (pin "8") (pinfunction "DP_8") (pintype "passive"))
      (node (ref "D22") (pin "25") (pinfunction "DP_25") (pintype "passive"))
      (node (ref "D22") (pin "6") (pinfunction "DP1_6") (pintype "passive"))
      (node (ref "D22") (pin "8") (pinfunction "DP_8") (pintype "passive"))
      (node (ref "D23") (pin "25") (pinfunction "DP_25") (pintype "passive"))
      (node (ref "D23") (pin "6") (pinfunction "DP1_6") (pintype "passive"))
      (node (ref "D23") (pin "8") (pinfunction "DP_8") (pintype "passive"))
      (node (ref "D24") (pin "25") (pinfunction "DP_25") (pintype "passive"))
      (node (ref "D24") (pin "6") (pinfunction "DP1_6") (pintype "passive"))
      (node (ref "D24") (pin "8") (pinfunction "DP_8") (pintype "passive"))
      (node (ref "D25") (pin "25") (pinfunction "DP_25") (pintype "passive"))
      (node (ref "D25") (pin "6") (pinfunction "DP1_6") (pintype "passive"))
      (node (ref "D25") (pin "8") (pinfunction "DP_8") (pintype "passive"))
      (node (ref "D26") (pin "25") (pinfunction "DP_25") (pintype "passive"))
      (node (ref "D26") (pin "6") (pinfunction "DP1_6") (pintype "passive"))
      (node (ref "D26") (pin "8") (pinfunction "DP_8") (pintype "passive"))
      (node (ref "D27") (pin "25") (pinfunction "DP_25") (pintype "passive"))
      (node (ref "D27") (pin "6") (pinfunction "DP1_6") (pintype "passive"))
      (node (ref "D27") (pin "8") (pinfunction "DP_8") (pintype "passive"))
      (node (ref "JP12") (pin "1") (pinfunction "1_1") (pintype "passive"))
      (node (ref "JP9") (pin "1") (pinfunction "1_1") (pintype "passive"))
    )
    (net (code "49") (name "SEG_DP_SOURCE") (class "Default")
      (node (ref "JP7") (pin "1") (pinfunction "1_1") (pintype "passive"))
      (node (ref "M11") (pin "3") (pinfunction "D_3") (pintype "passive"))
    )
    (net (code "50") (name "SEG_E") (class "Default")
      (node (ref "D14") (pin "21") (pinfunction "E_21") (pintype "passive"))
      (node (ref "D14") (pin "4") (pinfunction "E_4") (pintype "passive"))
      (node (ref "D15") (pin "21") (pinfunction "E_21") (pintype "passive"))
      (node (ref "D15") (pin "4") (pinfunction "E_4") (pintype "passive"))
      (node (ref "D16") (pin "21") (pinfunction "E_21") (pintype "passive"))
      (node (ref "D16") (pin "4") (pinfunction "E_4") (pintype "passive"))
      (node (ref "D17") (pin "21") (pinfunction "E_21") (pintype "passive"))
      (node (ref "D17") (pin "4") (pinfunction "E_4") (pintype "passive"))
      (node (ref "D18") (pin "21") (pinfunction "E_21") (pintype "passive"))
      (node (ref "D18") (pin "4") (pinfunction "E_4") (pintype "passive"))
      (node (ref "D19") (pin "21") (pinfunction "E_21") (pintype "passive"))
      (node (ref "D19") (pin "4") (pinfunction "E_4") (pintype "passive"))
      (node (ref "D2") (pin "21") (pinfunction "E_21") (pintype "passive"))
      (node (ref "D2") (pin "4") (pinfunction "E_4") (pintype "passive"))
      (node (ref "D20") (pin "21") (pinfunction "E_21") (pintype "passive"))
      (node (ref "D20") (pin "4") (pinfunction "E_4") (pintype "passive"))
      (node (ref "D21") (pin "21") (pinfunction "E_21") (pintype "passive"))
      (node (ref "D21") (pin "4") (pinfunction "E_4") (pintype "passive"))
      (node (ref "D22") (pin "21") (pinfunction "E_21") (pintype "passive"))
      (node (ref "D22") (pin "4") (pinfunction "E_4") (pintype "passive"))
      (node (ref "D23") (pin "21") (pinfunction "E_21") (pintype "passive"))
      (node (ref "D23") (pin "4") (pinfunction "E_4") (pintype "passive"))
      (node (ref "D24") (pin "21") (pinfunction "E_21") (pintype "passive"))
      (node (ref "D24") (pin "4") (pinfunction "E_4") (pintype "passive"))
      (node (ref "D25") (pin "21") (pinfunction "E_21") (pintype "passive"))
      (node (ref "D25") (pin "4") (pinfunction "E_4") (pintype "passive"))
      (node (ref "D26") (pin "21") (pinfunction "E_21") (pintype "passive"))
      (node (ref "D26") (pin "4") (pinfunction "E_4") (pintype "passive"))
      (node (ref "D27") (pin "21") (pinfunction "E_21") (pintype "passive"))
      (node (ref "D27") (pin "4") (pinfunction "E_4") (pintype "passive"))
      (node (ref "M8") (pin "3") (pinfunction "D_3") (pintype "passive"))
    )
    (net (code "51") (name "SEG_F") (class "Default")
      (node (ref "D14") (pin "2") (pinfunction "F_2") (pintype "passive"))
      (node (ref "D14") (pin "29") (pinfunction "F_29") (pintype "passive"))
      (node (ref "D15") (pin "2") (pinfunction "F_2") (pintype "passive"))
      (node (ref "D15") (pin "29") (pinfunction "F_29") (pintype "passive"))
      (node (ref "D16") (pin "2") (pinfunction "F_2") (pintype "passive"))
      (node (ref "D16") (pin "29") (pinfunction "F_29") (pintype "passive"))
      (node (ref "D17") (pin "2") (pinfunction "F_2") (pintype "passive"))
      (node (ref "D17") (pin "29") (pinfunction "F_29") (pintype "passive"))
      (node (ref "D18") (pin "2") (pinfunction "F_2") (pintype "passive"))
      (node (ref "D18") (pin "29") (pinfunction "F_29") (pintype "passive"))
      (node (ref "D19") (pin "2") (pinfunction "F_2") (pintype "passive"))
      (node (ref "D19") (pin "29") (pinfunction "F_29") (pintype "passive"))
      (node (ref "D2") (pin "2") (pinfunction "F_2") (pintype "passive"))
      (node (ref "D2") (pin "29") (pinfunction "F_29") (pintype "passive"))
      (node (ref "D20") (pin "2") (pinfunction "F_2") (pintype "passive"))
      (node (ref "D20") (pin "29") (pinfunction "F_29") (pintype "passive"))
      (node (ref "D21") (pin "2") (pinfunction "F_2") (pintype "passive"))
      (node (ref "D21") (pin "29") (pinfunction "F_29") (pintype "passive"))
      (node (ref "D22") (pin "2") (pinfunction "F_2") (pintype "passive"))
      (node (ref "D22") (pin "29") (pinfunction "F_29") (pintype "passive"))
      (node (ref "D23") (pin "2") (pinfunction "F_2") (pintype "passive"))
      (node (ref "D23") (pin "29") (pinfunction "F_29") (pintype "passive"))
      (node (ref "D24") (pin "2") (pinfunction "F_2") (pintype "passive"))
      (node (ref "D24") (pin "29") (pinfunction "F_29") (pintype "passive"))
      (node (ref "D25") (pin "2") (pinfunction "F_2") (pintype "passive"))
      (node (ref "D25") (pin "29") (pinfunction "F_29") (pintype "passive"))
      (node (ref "D26") (pin "2") (pinfunction "F_2") (pintype "passive"))
      (node (ref "D26") (pin "29") (pinfunction "F_29") (pintype "passive"))
      (node (ref "D27") (pin "2") (pinfunction "F_2") (pintype "passive"))
      (node (ref "D27") (pin "29") (pinfunction "F_29") (pintype "passive"))
      (node (ref "M9") (pin "3") (pinfunction "D_3") (pintype "passive"))
    )
    (net (code "52") (name "SEG_G") (class "Default")
      (node (ref "D14") (pin "1") (pinfunction "G1_1") (pintype "passive"))
      (node (ref "D14") (pin "3") (pinfunction "G_3") (pintype "passive"))
      (node (ref "D14") (pin "30") (pinfunction "G_30") (pintype "passive"))
      (node (ref "D15") (pin "1") (pinfunction "G1_1") (pintype "passive"))
      (node (ref "D15") (pin "3") (pinfunction "G_3") (pintype "passive"))
      (node (ref "D15") (pin "30") (pinfunction "G_30") (pintype "passive"))
      (node (ref "D16") (pin "1") (pinfunction "G1_1") (pintype "passive"))
      (node (ref "D16") (pin "3") (pinfunction "G_3") (pintype "passive"))
      (node (ref "D16") (pin "30") (pinfunction "G_30") (pintype "passive"))
      (node (ref "D17") (pin "1") (pinfunction "G1_1") (pintype "passive"))
      (node (ref "D17") (pin "3") (pinfunction "G_3") (pintype "passive"))
      (node (ref "D17") (pin "30") (pinfunction "G_30") (pintype "passive"))
      (node (ref "D18") (pin "1") (pinfunction "G1_1") (pintype "passive"))
      (node (ref "D18") (pin "3") (pinfunction "G_3") (pintype "passive"))
      (node (ref "D18") (pin "30") (pinfunction "G_30") (pintype "passive"))
      (node (ref "D19") (pin "1") (pinfunction "G1_1") (pintype "passive"))
      (node (ref "D19") (pin "3") (pinfunction "G_3") (pintype "passive"))
      (node (ref "D19") (pin "30") (pinfunction "G_30") (pintype "passive"))
      (node (ref "D2") (pin "1") (pinfunction "G1_1") (pintype "passive"))
      (node (ref "D2") (pin "3") (pinfunction "G_3") (pintype "passive"))
      (node (ref "D2") (pin "30") (pinfunction "G_30") (pintype "passive"))
      (node (ref "D20") (pin "1") (pinfunction "G1_1") (pintype "passive"))
      (node (ref "D20") (pin "3") (pinfunction "G_3") (pintype "passive"))
      (node (ref "D20") (pin "30") (pinfunction "G_30") (pintype "passive"))
      (node (ref "D21") (pin "1") (pinfunction "G1_1") (pintype "passive"))
      (node (ref "D21") (pin "3") (pinfunction "G_3") (pintype "passive"))
      (node (ref "D21") (pin "30") (pinfunction "G_30") (pintype "passive"))
      (node (ref "D22") (pin "1") (pinfunction "G1_1") (pintype "passive"))
      (node (ref "D22") (pin "3") (pinfunction "G_3") (pintype "passive"))
      (node (ref "D22") (pin "30") (pinfunction "G_30") (pintype "passive"))
      (node (ref "D23") (pin "1") (pinfunction "G1_1") (pintype "passive"))
      (node (ref "D23") (pin "3") (pinfunction "G_3") (pintype "passive"))
      (node (ref "D23") (pin "30") (pinfunction "G_30") (pintype "passive"))
      (node (ref "D24") (pin "1") (pinfunction "G1_1") (pintype "passive"))
      (node (ref "D24") (pin "3") (pinfunction "G_3") (pintype "passive"))
      (node (ref "D24") (pin "30") (pinfunction "G_30") (pintype "passive"))
      (node (ref "D25") (pin "1") (pinfunction "G1_1") (pintype "passive"))
      (node (ref "D25") (pin "3") (pinfunction "G_3") (pintype "passive"))
      (node (ref "D25") (pin "30") (pinfunction "G_30") (pintype "passive"))
      (node (ref "D26") (pin "1") (pinfunction "G1_1") (pintype "passive"))
      (node (ref "D26") (pin "3") (pinfunction "G_3") (pintype "passive"))
      (node (ref "D26") (pin "30") (pinfunction "G_30") (pintype "passive"))
      (node (ref "D27") (pin "1") (pinfunction "G1_1") (pintype "passive"))
      (node (ref "D27") (pin "3") (pinfunction "G_3") (pintype "passive"))
      (node (ref "D27") (pin "30") (pinfunction "G_30") (pintype "passive"))
      (node (ref "M10") (pin "3") (pinfunction "D_3") (pintype "passive"))
    )
  )
)
